# uLI-02.net
KiCad netlist of a schematic drawn in EAGLE
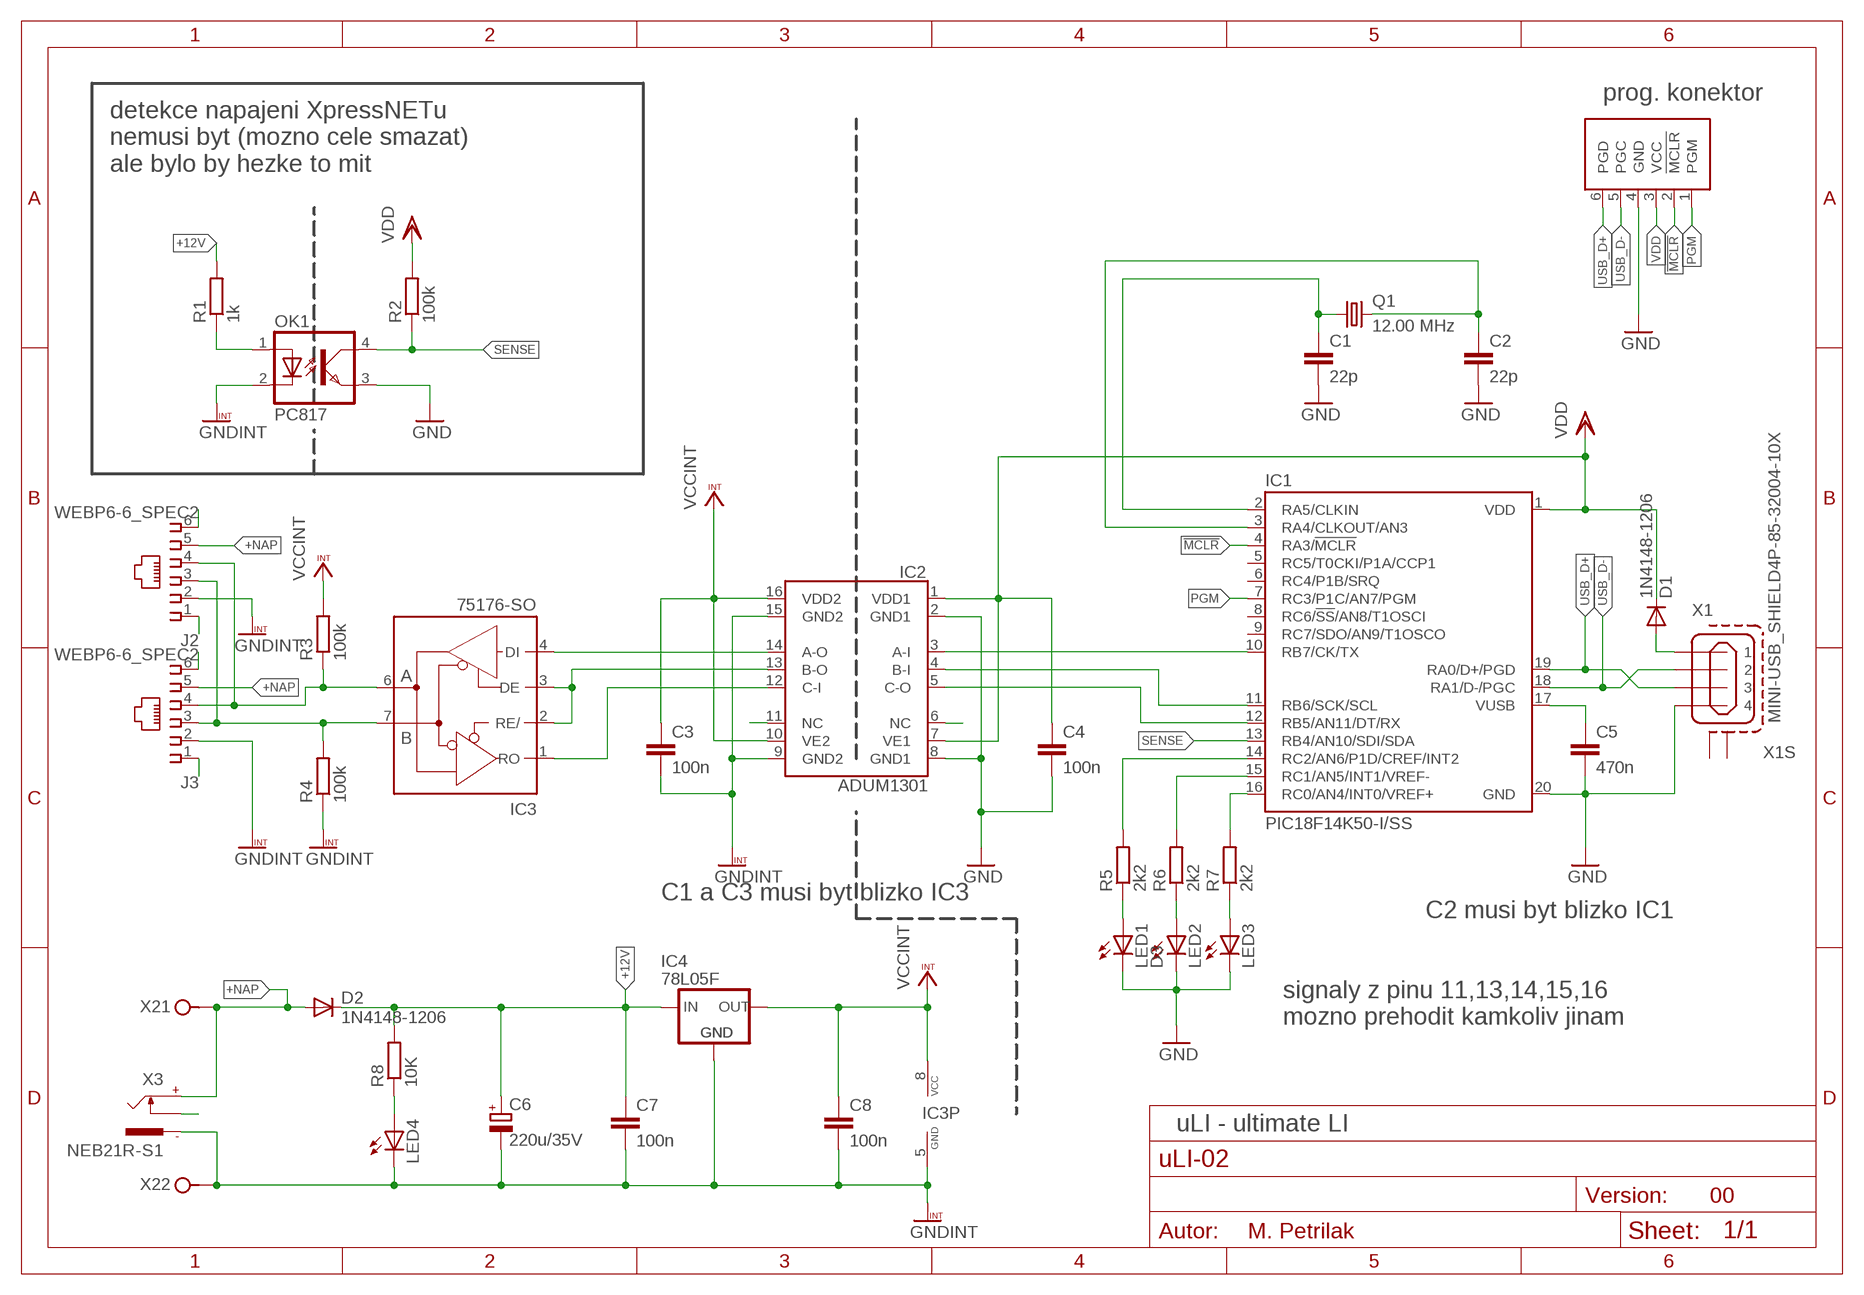
[diagram p0: schematic, sheet 1]

(export (version "E")
  (design (tool "Eeschema 10.0.6"))
  (components
    (comp (ref "C1")
      (value "22p")
      (footprint "eagle-import:C0805")
      (libsource (lib "eagle-import") (part "C-EUC0805"))
    )
    (comp (ref "C2")
      (value "22p")
      (footprint "eagle-import:C0805")
      (libsource (lib "eagle-import") (part "C-EUC0805"))
    )
    (comp (ref "C3")
      (value "100n")
      (footprint "eagle-import:C1206")
      (libsource (lib "eagle-import") (part "C-EUC1206"))
    )
    (comp (ref "C4")
      (value "100n")
      (footprint "eagle-import:C1206")
      (libsource (lib "eagle-import") (part "C-EUC1206"))
    )
    (comp (ref "C5")
      (value "470n")
      (footprint "eagle-import:C1206")
      (libsource (lib "eagle-import") (part "C-EUC1206"))
    )
    (comp (ref "C6")
      (value "220u/35V")
      (footprint "eagle-import:E3,5-8L")
      (libsource (lib "eagle-import") (part "CPOL-EUE3.5-8L"))
    )
    (comp (ref "C7")
      (value "100n")
      (footprint "eagle-import:C1206")
      (libsource (lib "eagle-import") (part "C-EUC1206"))
    )
    (comp (ref "C8")
      (value "100n")
      (footprint "eagle-import:C1206")
      (libsource (lib "eagle-import") (part "C-EUC1206"))
    )
    (comp (ref "D1")
      (value "1N4148-1206")
      (footprint "eagle-import:D1206")
      (libsource (lib "eagle-import") (part "1N4148-1206"))
    )
    (comp (ref "D2")
      (value "1N4148-1206")
      (footprint "eagle-import:D1206")
      (libsource (lib "eagle-import") (part "1N4148-1206"))
    )
    (comp (ref "IC1")
      (value "PIC18F14K50-I/SS")
      (footprint "eagle-import:SSOP20")
      (libsource (lib "eagle-import") (part "PIC18K50-I/SSF14"))
    )
    (comp (ref "IC2")
      (value "ADUM1301")
      (footprint "eagle-import:SO-16W")
      (libsource (lib "eagle-import") (part "ADUM1301"))
    )
    (comp (ref "IC3")
      (value "75176-SO")
      (footprint "eagle-import:SO08")
      (libsource (lib "eagle-import") (part "75176-SO"))
    )
    (comp (ref "IC4")
      (value "78L05F")
      (footprint "eagle-import:SOT89")
      (libsource (lib "eagle-import") (part "78LF05"))
    )
    (comp (ref "J1")
      (value "PICPROG2-V")
      (footprint "eagle-import:6410-06-PICPROG")
      (libsource (lib "eagle-import") (part "PICPROG2-V"))
    )
    (comp (ref "J2")
      (value "WEBP6-6_SPEC2")
      (footprint "eagle-import:WEBP6-6_SPEC2")
      (libsource (lib "eagle-import") (part "WEBP6-6_SPEC2"))
    )
    (comp (ref "J3")
      (value "WEBP6-6_SPEC2")
      (footprint "eagle-import:WEBP6-6_SPEC2")
      (libsource (lib "eagle-import") (part "WEBP6-6_SPEC2"))
    )
    (comp (ref "LED1")
      (value "D3")
      (footprint "eagle-import:LED3MM")
      (libsource (lib "eagle-import") (part "LED3MM"))
    )
    (comp (ref "LED2")
      (value "LED3MM")
      (footprint "eagle-import:LED3MM")
      (libsource (lib "eagle-import") (part "LED3MM"))
    )
    (comp (ref "LED3")
      (value "LED3MM")
      (footprint "eagle-import:LED3MM")
      (libsource (lib "eagle-import") (part "LED3MM"))
    )
    (comp (ref "LED4")
      (value "LED3MM")
      (footprint "eagle-import:LED3MM")
      (libsource (lib "eagle-import") (part "LED3MM"))
    )
    (comp (ref "OK1")
      (value "PC817")
      (footprint "eagle-import:DIL04")
      (libsource (lib "eagle-import") (part "PC817"))
    )
    (comp (ref "Q1")
      (value "12.00 MHz")
      (footprint "eagle-import:HC49U70")
      (libsource (lib "eagle-import") (part "XTAL"))
    )
    (comp (ref "R1")
      (value "1k")
      (footprint "eagle-import:R1206")
      (libsource (lib "eagle-import") (part "R-EU_R1206"))
    )
    (comp (ref "R2")
      (value "100k")
      (footprint "eagle-import:R1206")
      (libsource (lib "eagle-import") (part "R-EU_R1206"))
    )
    (comp (ref "R3")
      (value "100k")
      (footprint "eagle-import:R1206")
      (libsource (lib "eagle-import") (part "R-EU_R1206"))
    )
    (comp (ref "R4")
      (value "100k")
      (footprint "eagle-import:R1206")
      (libsource (lib "eagle-import") (part "R-EU_R1206"))
    )
    (comp (ref "R5")
      (value "2k2")
      (footprint "eagle-import:R1206")
      (libsource (lib "eagle-import") (part "R-EU_R1206"))
    )
    (comp (ref "R6")
      (value "2k2")
      (footprint "eagle-import:R1206")
      (libsource (lib "eagle-import") (part "R-EU_R1206"))
    )
    (comp (ref "R7")
      (value "2k2")
      (footprint "eagle-import:R1206")
      (libsource (lib "eagle-import") (part "R-EU_R1206"))
    )
    (comp (ref "R8")
      (value "10K")
      (footprint "eagle-import:R1206")
      (libsource (lib "eagle-import") (part "R-EU_R1206"))
    )
    (comp (ref "X1")
      (value "MINI-USB_SHIELD4P-85-32004-10X")
      (footprint "eagle-import:85-32004-10X")
      (libsource (lib "eagle-import") (part "MINI-USB_SHIELD4P-85-32004-10X"))
    )
    (comp (ref "X2")
      (value "ARK1550/2_S")
      (footprint "eagle-import:ARK1550_2_SPEC")
      (libsource (lib "eagle-import") (part "ARK1550/2_S"))
    )
    (comp (ref "X3")
      (value "NEB21R-S1")
      (footprint "eagle-import:NEB21R_SPEC")
      (libsource (lib "eagle-import") (part "NEB21R-S1"))
    )
  )
  (nets
    (net (code "1") (name "+12V") (class "Default")
      (node (ref "C6") (pin "+") (pinfunction "+_+") (pintype "passive"))
      (node (ref "C7") (pin "1") (pinfunction "1_1") (pintype "passive"))
      (node (ref "D2") (pin "C") (pinfunction "C_C") (pintype "passive"))
      (node (ref "IC4") (pin "3") (pinfunction "VI_3") (pintype "input"))
      (node (ref "R1") (pin "2") (pinfunction "2_2") (pintype "passive"))
      (node (ref "R8") (pin "2") (pinfunction "2_2") (pintype "passive"))
    )
    (net (code "2") (name "+NAP") (class "Default")
      (node (ref "D2") (pin "A") (pinfunction "A_A") (pintype "passive"))
      (node (ref "J2") (pin "5") (pinfunction "5_5") (pintype "passive"))
      (node (ref "J3") (pin "5") (pinfunction "5_5") (pintype "passive"))
      (node (ref "X2") (pin "1") (pinfunction "1_1") (pintype "passive"))
      (node (ref "X3") (pin "+") (pinfunction "+_+") (pintype "passive"))
    )
    (net (code "3") (name "/~{MCLR}") (class "Default")
      (node (ref "IC1") (pin "4") (pinfunction "RA3/~{MCLR}_4") (pintype "bidirectional"))
      (node (ref "J1") (pin "2") (pinfunction "~{MCLR}_2") (pintype "output"))
    )
    (net (code "4") (name "GND") (class "Default")
      (node (ref "C1") (pin "2") (pinfunction "2_2") (pintype "passive"))
      (node (ref "C2") (pin "2") (pinfunction "2_2") (pintype "passive"))
      (node (ref "C4") (pin "2") (pinfunction "2_2") (pintype "passive"))
      (node (ref "C5") (pin "2") (pinfunction "2_2") (pintype "passive"))
      (node (ref "IC1") (pin "20") (pinfunction "GND_20") (pintype "power_in"))
      (node (ref "IC2") (pin "2") (pinfunction "GND1_2") (pintype "power_in"))
      (node (ref "IC2") (pin "8") (pinfunction "GND1_8") (pintype "power_in"))
      (node (ref "J1") (pin "4") (pinfunction "GND_4") (pintype "power_in"))
      (node (ref "LED1") (pin "K") (pinfunction "C_K") (pintype "passive"))
      (node (ref "LED2") (pin "K") (pinfunction "C_K") (pintype "passive"))
      (node (ref "LED3") (pin "K") (pinfunction "C_K") (pintype "passive"))
      (node (ref "OK1") (pin "3") (pinfunction "EMIT_3") (pintype "passive"))
      (node (ref "X1") (pin "4") (pinfunction "4_4") (pintype "passive"))
    )
    (net (code "5") (name "GNDINT") (class "Default")
      (node (ref "C3") (pin "2") (pinfunction "2_2") (pintype "passive"))
      (node (ref "C6") (pin "-") (pinfunction "-_-") (pintype "passive"))
      (node (ref "C7") (pin "2") (pinfunction "2_2") (pintype "passive"))
      (node (ref "C8") (pin "2") (pinfunction "2_2") (pintype "passive"))
      (node (ref "IC2") (pin "15") (pinfunction "GND2_15") (pintype "power_in"))
      (node (ref "IC2") (pin "9") (pinfunction "GND2_9") (pintype "power_in"))
      (node (ref "IC3") (pin "5") (pinfunction "GND_5") (pintype "power_in"))
      (node (ref "IC4") (pin "2") (pinfunction "GND_2") (pintype "passive"))
      (node (ref "IC4") (pin "2@1") (pinfunction "GND_2@1") (pintype "passive"))
      (node (ref "J2") (pin "2") (pinfunction "2_2") (pintype "passive"))
      (node (ref "J3") (pin "2") (pinfunction "2_2") (pintype "passive"))
      (node (ref "LED4") (pin "K") (pinfunction "C_K") (pintype "passive"))
      (node (ref "OK1") (pin "2") (pinfunction "C_2") (pintype "passive"))
      (node (ref "R4") (pin "1") (pinfunction "1_1") (pintype "passive"))
      (node (ref "X2") (pin "2") (pinfunction "1_2") (pintype "passive"))
      (node (ref "X3") (pin "-") (pinfunction "-_-") (pintype "passive"))
    )
    (net (code "6") (name "Net-(D1-PadA)") (class "Default")
      (node (ref "D1") (pin "A") (pinfunction "A_A") (pintype "passive"))
      (node (ref "X1") (pin "1") (pinfunction "1_1") (pintype "passive"))
    )
    (net (code "7") (name "Net-(IC1-RA4{slash}CLKOUT{slash}AN3)") (class "Default")
      (node (ref "C2") (pin "1") (pinfunction "1_1") (pintype "passive"))
      (node (ref "IC1") (pin "3") (pinfunction "RA4/CLKOUT/AN3_3") (pintype "bidirectional"))
      (node (ref "Q1") (pin "2") (pinfunction "2_2") (pintype "passive"))
    )
    (net (code "8") (name "Net-(IC1-RA5{slash}CLKIN)") (class "Default")
      (node (ref "C1") (pin "1") (pinfunction "1_1") (pintype "passive"))
      (node (ref "IC1") (pin "2") (pinfunction "RA5/CLKIN_2") (pintype "bidirectional"))
      (node (ref "Q1") (pin "1") (pinfunction "1_1") (pintype "passive"))
    )
    (net (code "9") (name "Net-(IC1-RB5{slash}AN11{slash}DT{slash}RX)") (class "Default")
      (node (ref "IC1") (pin "12") (pinfunction "RB5/AN11/DT/RX_12") (pintype "bidirectional"))
      (node (ref "IC2") (pin "5") (pinfunction "C-O_5") (pintype "output"))
    )
    (net (code "10") (name "Net-(IC1-RB6{slash}SCK{slash}SCL)") (class "Default")
      (node (ref "IC1") (pin "11") (pinfunction "RB6/SCK/SCL_11") (pintype "bidirectional"))
      (node (ref "IC2") (pin "4") (pinfunction "B-I_4") (pintype "input"))
    )
    (net (code "11") (name "Net-(IC1-RB7{slash}CK{slash}TX)") (class "Default")
      (node (ref "IC1") (pin "10") (pinfunction "RB7/CK/TX_10") (pintype "bidirectional"))
      (node (ref "IC2") (pin "3") (pinfunction "A-I_3") (pintype "input"))
    )
    (net (code "12") (name "Net-(IC1-RC0{slash}AN4{slash}INT0{slash}VREF+)") (class "Default")
      (node (ref "IC1") (pin "16") (pinfunction "RC0/AN4/INT0/VREF+_16") (pintype "bidirectional"))
      (node (ref "R7") (pin "2") (pinfunction "2_2") (pintype "passive"))
    )
    (net (code "13") (name "Net-(IC1-RC1{slash}AN5{slash}INT1{slash}VREF-)") (class "Default")
      (node (ref "IC1") (pin "15") (pinfunction "RC1/AN5/INT1/VREF-_15") (pintype "bidirectional"))
      (node (ref "R6") (pin "2") (pinfunction "2_2") (pintype "passive"))
    )
    (net (code "14") (name "Net-(IC1-RC2{slash}AN6{slash}P1D{slash}CREF{slash}INT2)") (class "Default")
      (node (ref "IC1") (pin "14") (pinfunction "RC2/AN6/P1D/CREF/INT2_14") (pintype "bidirectional"))
      (node (ref "R5") (pin "2") (pinfunction "2_2") (pintype "passive"))
    )
    (net (code "15") (name "Net-(IC1-VUSB)") (class "Default")
      (node (ref "C5") (pin "1") (pinfunction "1_1") (pintype "passive"))
      (node (ref "IC1") (pin "17") (pinfunction "VUSB_17") (pintype "bidirectional"))
    )
    (net (code "16") (name "Net-(IC2-A-O)") (class "Default")
      (node (ref "IC2") (pin "14") (pinfunction "A-O_14") (pintype "output"))
      (node (ref "IC3") (pin "4") (pinfunction "DI_4") (pintype "input"))
    )
    (net (code "17") (name "Net-(IC2-B-O)") (class "Default")
      (node (ref "IC2") (pin "13") (pinfunction "B-O_13") (pintype "output"))
      (node (ref "IC3") (pin "2") (pinfunction "RE/_2") (pintype "input"))
      (node (ref "IC3") (pin "3") (pinfunction "DE_3") (pintype "input"))
    )
    (net (code "18") (name "Net-(IC2-C-I)") (class "Default")
      (node (ref "IC2") (pin "12") (pinfunction "C-I_12") (pintype "input"))
      (node (ref "IC3") (pin "1") (pinfunction "RO_1") (pintype "output"))
    )
    (net (code "19") (name "Net-(IC3A-A)") (class "Default")
      (node (ref "IC3") (pin "6") (pinfunction "A_6") (pintype "passive"))
      (node (ref "J2") (pin "4") (pinfunction "4_4") (pintype "passive"))
      (node (ref "J3") (pin "4") (pinfunction "4_4") (pintype "passive"))
      (node (ref "R3") (pin "1") (pinfunction "1_1") (pintype "passive"))
    )
    (net (code "20") (name "Net-(IC3A-B)") (class "Default")
      (node (ref "IC3") (pin "7") (pinfunction "B_7") (pintype "passive"))
      (node (ref "J2") (pin "3") (pinfunction "3_3") (pintype "passive"))
      (node (ref "J3") (pin "3") (pinfunction "3_3") (pintype "passive"))
      (node (ref "R4") (pin "2") (pinfunction "2_2") (pintype "passive"))
    )
    (net (code "21") (name "Net-(LED1-PadA)") (class "Default")
      (node (ref "LED1") (pin "A") (pinfunction "A_A") (pintype "passive"))
      (node (ref "R5") (pin "1") (pinfunction "1_1") (pintype "passive"))
    )
    (net (code "22") (name "Net-(LED2-PadA)") (class "Default")
      (node (ref "LED2") (pin "A") (pinfunction "A_A") (pintype "passive"))
      (node (ref "R6") (pin "1") (pinfunction "1_1") (pintype "passive"))
    )
    (net (code "23") (name "Net-(LED3-PadA)") (class "Default")
      (node (ref "LED3") (pin "A") (pinfunction "A_A") (pintype "passive"))
      (node (ref "R7") (pin "1") (pinfunction "1_1") (pintype "passive"))
    )
    (net (code "24") (name "Net-(LED4-PadA)") (class "Default")
      (node (ref "LED4") (pin "A") (pinfunction "A_A") (pintype "passive"))
      (node (ref "R8") (pin "1") (pinfunction "1_1") (pintype "passive"))
    )
    (net (code "25") (name "Net-(OK1-A)") (class "Default")
      (node (ref "OK1") (pin "1") (pinfunction "A_1") (pintype "passive"))
      (node (ref "R1") (pin "1") (pinfunction "1_1") (pintype "passive"))
    )
    (net (code "26") (name "PGM") (class "Default")
      (node (ref "IC1") (pin "7") (pinfunction "RC3/P1C/AN7/PGM_7") (pintype "bidirectional"))
      (node (ref "J1") (pin "1") (pinfunction "PGM_1") (pintype "output"))
    )
    (net (code "27") (name "SENSE") (class "Default")
      (node (ref "IC1") (pin "13") (pinfunction "RB4/AN10/SDI/SDA_13") (pintype "bidirectional"))
      (node (ref "OK1") (pin "4") (pinfunction "COL_4") (pintype "passive"))
      (node (ref "R2") (pin "1") (pinfunction "1_1") (pintype "passive"))
    )
    (net (code "28") (name "USB_D+") (class "Default")
      (node (ref "IC1") (pin "19") (pinfunction "RA0/D+/PGD_19") (pintype "bidirectional"))
      (node (ref "J1") (pin "6") (pinfunction "PGD_6") (pintype "input"))
      (node (ref "X1") (pin "3") (pinfunction "3_3") (pintype "passive"))
    )
    (net (code "29") (name "USB_D-") (class "Default")
      (node (ref "IC1") (pin "18") (pinfunction "RA1/D-/PGC_18") (pintype "bidirectional"))
      (node (ref "J1") (pin "5") (pinfunction "PGC_5") (pintype "output"))
      (node (ref "X1") (pin "2") (pinfunction "2_2") (pintype "passive"))
    )
    (net (code "30") (name "VCCINT") (class "Default")
      (node (ref "C3") (pin "1") (pinfunction "1_1") (pintype "passive"))
      (node (ref "C8") (pin "1") (pinfunction "1_1") (pintype "passive"))
      (node (ref "IC2") (pin "10") (pinfunction "VE2_10") (pintype "input"))
      (node (ref "IC2") (pin "16") (pinfunction "VDD2_16") (pintype "power_in"))
      (node (ref "IC3") (pin "8") (pinfunction "VCC_8") (pintype "power_in"))
      (node (ref "IC4") (pin "1") (pinfunction "VO_1") (pintype "passive"))
      (node (ref "R3") (pin "2") (pinfunction "2_2") (pintype "passive"))
    )
    (net (code "31") (name "VDD") (class "Default")
      (node (ref "C4") (pin "1") (pinfunction "1_1") (pintype "passive"))
      (node (ref "D1") (pin "C") (pinfunction "C_C") (pintype "passive"))
      (node (ref "IC1") (pin "1") (pinfunction "VDD_1") (pintype "power_in"))
      (node (ref "IC2") (pin "1") (pinfunction "VDD1_1") (pintype "power_in"))
      (node (ref "IC2") (pin "7") (pinfunction "VE1_7") (pintype "input"))
      (node (ref "J1") (pin "3") (pinfunction "VCC_3") (pintype "power_in"))
      (node (ref "R2") (pin "2") (pinfunction "2_2") (pintype "passive"))
    )
    (net (code "32") (name "unconnected-(IC1-RC4{slash}P1B{slash}SRQ-Pad6)") (class "Default")
      (node (ref "IC1") (pin "6") (pinfunction "RC4/P1B/SRQ_6") (pintype "bidirectional"))
    )
    (net (code "33") (name "unconnected-(IC1-RC5{slash}T0CKI{slash}P1A{slash}CCP1-Pad5)") (class "Default")
      (node (ref "IC1") (pin "5") (pinfunction "RC5/T0CKI/P1A/CCP1_5") (pintype "bidirectional"))
    )
    (net (code "34") (name "unconnected-(IC1-RC6{slash}~{SS}{slash}AN8{slash}T1OSCI-Pad8)") (class "Default")
      (node (ref "IC1") (pin "8") (pinfunction "RC6/~{SS}/AN8/T1OSCI_8") (pintype "bidirectional"))
    )
    (net (code "35") (name "unconnected-(IC1-RC7{slash}SDO{slash}AN9{slash}T1OSCO-Pad9)") (class "Default")
      (node (ref "IC1") (pin "9") (pinfunction "RC7/SDO/AN9/T1OSCO_9") (pintype "bidirectional"))
    )
    (net (code "36") (name "unconnected-(IC2-NC-Pad6)") (class "Default")
      (node (ref "IC2") (pin "6") (pinfunction "NC_6") (pintype "passive"))
    )
    (net (code "37") (name "unconnected-(IC2-NC-Pad11)") (class "Default")
      (node (ref "IC2") (pin "11") (pinfunction "NC_11") (pintype "passive"))
    )
    (net (code "38") (name "unconnected-(J2-Pad1)") (class "Default")
      (node (ref "J2") (pin "1") (pinfunction "1_1") (pintype "passive"))
    )
    (net (code "39") (name "unconnected-(J2-Pad6)") (class "Default")
      (node (ref "J2") (pin "6") (pinfunction "6_6") (pintype "passive"))
    )
    (net (code "40") (name "unconnected-(J3-Pad1)") (class "Default")
      (node (ref "J3") (pin "1") (pinfunction "1_1") (pintype "passive"))
    )
    (net (code "41") (name "unconnected-(J3-Pad6)") (class "Default")
      (node (ref "J3") (pin "6") (pinfunction "6_6") (pintype "passive"))
    )
    (net (code "42") (name "unconnected-(X1B-S1-PadM1)") (class "Default")
      (node (ref "X1") (pin "M1") (pinfunction "S1_M1") (pintype "passive"))
    )
    (net (code "43") (name "unconnected-(X1B-S2-PadM2)") (class "Default")
      (node (ref "X1") (pin "M2") (pinfunction "S2_M2") (pintype "passive"))
    )
    (net (code "44") (name "unconnected-(X3-PadC)") (class "Default")
      (node (ref "X3") (pin "C") (pinfunction "C_C") (pintype "passive"))
    )
  )
)
